# FPGA_bank0_vss.net
KiCad netlist of a schematic drawn in Altium Designer
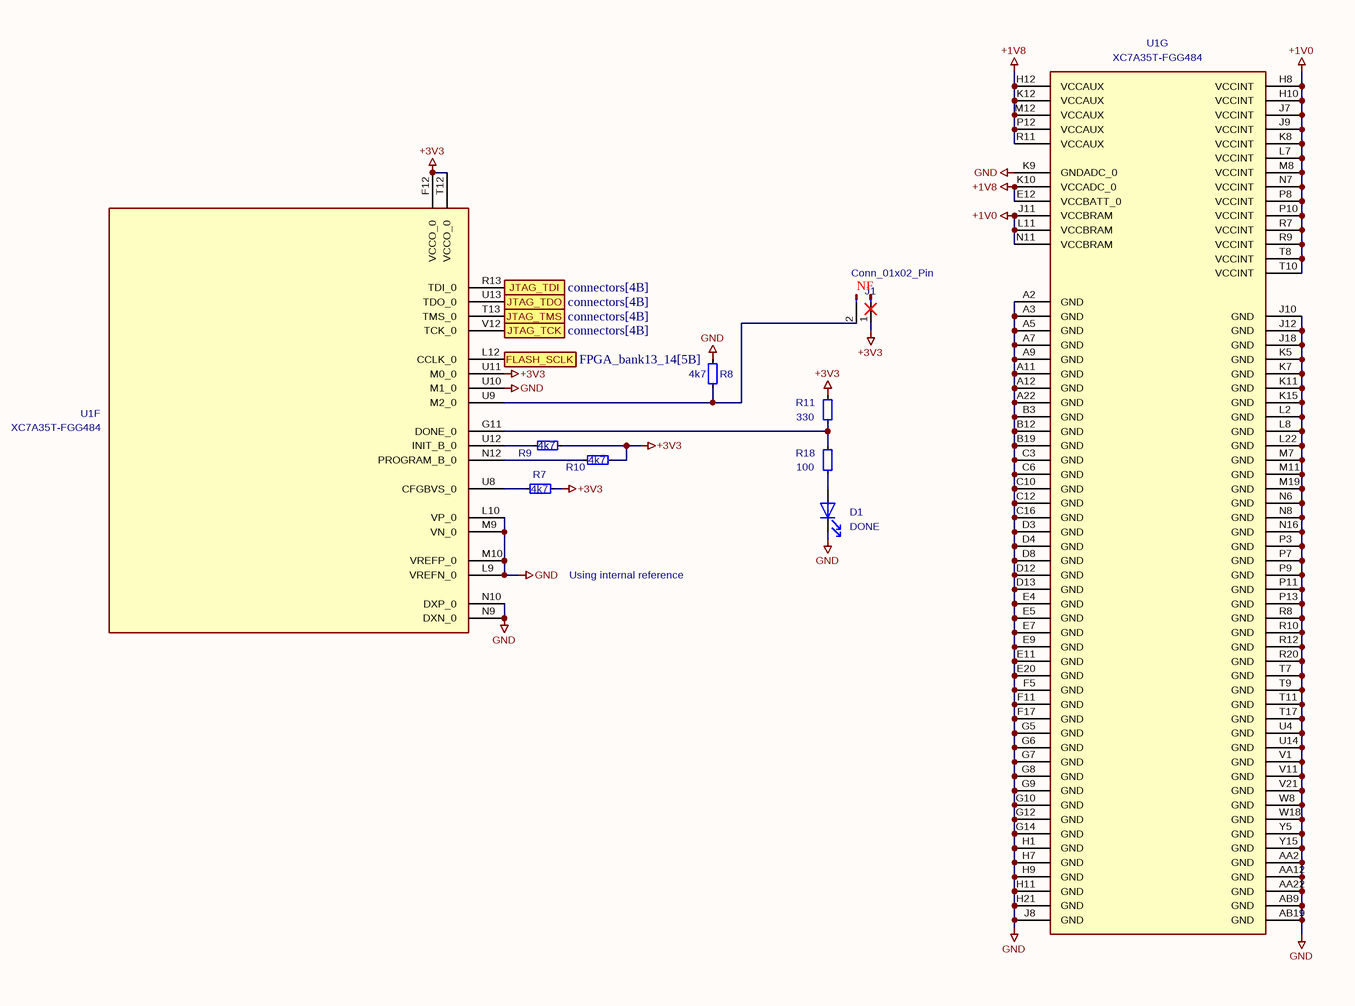
[diagram p0: FPGA_bank0_vss.SchDoc]

(export (version "E")
  (design (tool "Eeschema 10.0.6"))
  (components
    (comp (ref "D1") (value "DONE") (footprint "LED_0603_1608Metric") (libsource (lib "Device") (part "LED")))
    (comp (ref "J1")
      (value "Conn_01x02_Pin")
      (footprint "PinHeader_1x02_P2.54mm_Vertical")
      (libsource (lib "Connector") (part "Conn_01x02_Pin"))
    )
    (comp (ref "R7") (value "4k7") (footprint "R_0402_1005Metric") (libsource (lib "") (part "R_Small_1")))
    (comp (ref "R8")
      (value "4k7")
      (footprint "R_0402_1005Metric")
      (libsource (lib "Device") (part "R_Small"))
    )
    (comp (ref "R9") (value "4k7") (footprint "R_0402_1005Metric") (libsource (lib "") (part "R_Small_1")))
    (comp (ref "R10") (value "4k7") (footprint "R_0402_1005Metric") (libsource (lib "") (part "R_Small_1")))
    (comp (ref "R11")
      (value "330")
      (footprint "R_0402_1005Metric")
      (libsource (lib "Device") (part "R_Small"))
    )
    (comp (ref "R18")
      (value "100")
      (footprint "R_0402_1005Metric")
      (libsource (lib "Device") (part "R_Small"))
    )
    (comp (ref "U1")
      (value "XC7A35T-FGG484")
      (footprint "FB-BGA-484_23.0x23.0mm_Layout22x22_P1.0mm")
      (libsource (lib "som_fpga") (part "XC7A35T-FGG484"))
    )
  )
  (nets
    (net (code "1") (name "+1V0") (class "Default")
      (node (ref "U1") (pin "H10") (pinfunction "VCCINT_H10") (pintype "passive"))
      (node (ref "U1") (pin "H8") (pinfunction "VCCINT_H8") (pintype "passive"))
      (node (ref "U1") (pin "J11") (pinfunction "VCCBRAM_J11") (pintype "passive"))
      (node (ref "U1") (pin "J7") (pinfunction "VCCINT_J7") (pintype "passive"))
      (node (ref "U1") (pin "J9") (pinfunction "VCCINT_J9") (pintype "passive"))
      (node (ref "U1") (pin "K8") (pinfunction "VCCINT_K8") (pintype "passive"))
      (node (ref "U1") (pin "L11") (pinfunction "VCCBRAM_L11") (pintype "passive"))
      (node (ref "U1") (pin "L7") (pinfunction "VCCINT_L7") (pintype "passive"))
      (node (ref "U1") (pin "M8") (pinfunction "VCCINT_M8") (pintype "passive"))
      (node (ref "U1") (pin "N11") (pinfunction "VCCBRAM_N11") (pintype "passive"))
      (node (ref "U1") (pin "N7") (pinfunction "VCCINT_N7") (pintype "passive"))
      (node (ref "U1") (pin "P10") (pinfunction "VCCINT_P10") (pintype "passive"))
      (node (ref "U1") (pin "P8") (pinfunction "VCCINT_P8") (pintype "passive"))
      (node (ref "U1") (pin "R7") (pinfunction "VCCINT_R7") (pintype "passive"))
      (node (ref "U1") (pin "R9") (pinfunction "VCCINT_R9") (pintype "passive"))
      (node (ref "U1") (pin "T10") (pinfunction "VCCINT_T10") (pintype "passive"))
      (node (ref "U1") (pin "T8") (pinfunction "VCCINT_T8") (pintype "passive"))
    )
    (net (code "2") (name "+1V8") (class "Default")
      (node (ref "U1") (pin "E12") (pinfunction "VCCBATT_0_E12") (pintype "passive"))
      (node (ref "U1") (pin "H12") (pinfunction "VCCAUX_H12") (pintype "passive"))
      (node (ref "U1") (pin "K10") (pinfunction "VCCADC_0_K10") (pintype "passive"))
      (node (ref "U1") (pin "K12") (pinfunction "VCCAUX_K12") (pintype "passive"))
      (node (ref "U1") (pin "M12") (pinfunction "VCCAUX_M12") (pintype "passive"))
      (node (ref "U1") (pin "P12") (pinfunction "VCCAUX_P12") (pintype "passive"))
      (node (ref "U1") (pin "R11") (pinfunction "VCCAUX_R11") (pintype "passive"))
    )
    (net (code "3") (name "+3V3") (class "Default")
      (node (ref "J1") (pin "1") (pinfunction "Pin_1_1") (pintype "passive"))
      (node (ref "R10") (pin "2") (pinfunction "2_2") (pintype "passive"))
      (node (ref "R11") (pin "2") (pinfunction "2_2") (pintype "passive"))
      (node (ref "R7") (pin "2") (pinfunction "2_2") (pintype "passive"))
      (node (ref "R9") (pin "2") (pinfunction "2_2") (pintype "passive"))
      (node (ref "U1") (pin "F12") (pinfunction "VCCO_0_F12") (pintype "passive"))
      (node (ref "U1") (pin "T12") (pinfunction "VCCO_0_T12") (pintype "passive"))
      (node (ref "U1") (pin "U11") (pinfunction "M0_0_U11") (pintype "passive"))
    )
    (net (code "4") (name "/FLASH_SCLK") (class "Default")
      (node (ref "U1") (pin "L12") (pinfunction "CCLK_0_L12") (pintype "passive"))
    )
    (net (code "5") (name "/JTAG_TCK") (class "Default")
      (node (ref "U1") (pin "V12") (pinfunction "TCK_0_V12") (pintype "passive"))
    )
    (net (code "6") (name "/JTAG_TDI") (class "Default")
      (node (ref "U1") (pin "R13") (pinfunction "TDI_0_R13") (pintype "passive"))
    )
    (net (code "7") (name "/JTAG_TDO") (class "Default")
      (node (ref "U1") (pin "U13") (pinfunction "TDO_0_U13") (pintype "passive"))
    )
    (net (code "8") (name "/JTAG_TMS") (class "Default")
      (node (ref "U1") (pin "T13") (pinfunction "TMS_0_T13") (pintype "passive"))
    )
    (net (code "9") (name "GND") (class "Default")
      (node (ref "D1") (pin "1") (pinfunction "K_1") (pintype "passive"))
      (node (ref "R8") (pin "2") (pinfunction "2_2") (pintype "passive"))
      (node (ref "U1") (pin "A11") (pinfunction "GND_A11") (pintype "passive"))
      (node (ref "U1") (pin "A12") (pinfunction "GND_A12") (pintype "passive"))
      (node (ref "U1") (pin "A2") (pinfunction "GND_A2") (pintype "passive"))
      (node (ref "U1") (pin "A22") (pinfunction "GND_A22") (pintype "passive"))
      (node (ref "U1") (pin "A3") (pinfunction "GND_A3") (pintype "passive"))
      (node (ref "U1") (pin "A5") (pinfunction "GND_A5") (pintype "passive"))
      (node (ref "U1") (pin "A7") (pinfunction "GND_A7") (pintype "passive"))
      (node (ref "U1") (pin "A9") (pinfunction "GND_A9") (pintype "passive"))
      (node (ref "U1") (pin "AA12") (pinfunction "GND_AA12") (pintype "passive"))
      (node (ref "U1") (pin "AA2") (pinfunction "GND_AA2") (pintype "passive"))
      (node (ref "U1") (pin "AA22") (pinfunction "GND_AA22") (pintype "passive"))
      (node (ref "U1") (pin "AB19") (pinfunction "GND_AB19") (pintype "passive"))
      (node (ref "U1") (pin "AB9") (pinfunction "GND_AB9") (pintype "passive"))
      (node (ref "U1") (pin "B12") (pinfunction "GND_B12") (pintype "passive"))
      (node (ref "U1") (pin "B19") (pinfunction "GND_B19") (pintype "passive"))
      (node (ref "U1") (pin "B3") (pinfunction "GND_B3") (pintype "passive"))
      (node (ref "U1") (pin "C10") (pinfunction "GND_C10") (pintype "passive"))
      (node (ref "U1") (pin "C12") (pinfunction "GND_C12") (pintype "passive"))
      (node (ref "U1") (pin "C16") (pinfunction "GND_C16") (pintype "passive"))
      (node (ref "U1") (pin "C3") (pinfunction "GND_C3") (pintype "passive"))
      (node (ref "U1") (pin "C6") (pinfunction "GND_C6") (pintype "passive"))
      (node (ref "U1") (pin "D12") (pinfunction "GND_D12") (pintype "passive"))
      (node (ref "U1") (pin "D13") (pinfunction "GND_D13") (pintype "passive"))
      (node (ref "U1") (pin "D3") (pinfunction "GND_D3") (pintype "passive"))
      (node (ref "U1") (pin "D4") (pinfunction "GND_D4") (pintype "passive"))
      (node (ref "U1") (pin "D8") (pinfunction "GND_D8") (pintype "passive"))
      (node (ref "U1") (pin "E11") (pinfunction "GND_E11") (pintype "passive"))
      (node (ref "U1") (pin "E20") (pinfunction "GND_E20") (pintype "passive"))
      (node (ref "U1") (pin "E4") (pinfunction "GND_E4") (pintype "passive"))
      (node (ref "U1") (pin "E5") (pinfunction "GND_E5") (pintype "passive"))
      (node (ref "U1") (pin "E7") (pinfunction "GND_E7") (pintype "passive"))
      (node (ref "U1") (pin "E9") (pinfunction "GND_E9") (pintype "passive"))
      (node (ref "U1") (pin "F11") (pinfunction "GND_F11") (pintype "passive"))
      (node (ref "U1") (pin "F17") (pinfunction "GND_F17") (pintype "passive"))
      (node (ref "U1") (pin "F5") (pinfunction "GND_F5") (pintype "passive"))
      (node (ref "U1") (pin "G10") (pinfunction "GND_G10") (pintype "passive"))
      (node (ref "U1") (pin "G12") (pinfunction "GND_G12") (pintype "passive"))
      (node (ref "U1") (pin "G14") (pinfunction "GND_G14") (pintype "passive"))
      (node (ref "U1") (pin "G5") (pinfunction "GND_G5") (pintype "passive"))
      (node (ref "U1") (pin "G6") (pinfunction "GND_G6") (pintype "passive"))
      (node (ref "U1") (pin "G7") (pinfunction "GND_G7") (pintype "passive"))
      (node (ref "U1") (pin "G8") (pinfunction "GND_G8") (pintype "passive"))
      (node (ref "U1") (pin "G9") (pinfunction "GND_G9") (pintype "passive"))
      (node (ref "U1") (pin "H1") (pinfunction "GND_H1") (pintype "passive"))
      (node (ref "U1") (pin "H11") (pinfunction "GND_H11") (pintype "passive"))
      (node (ref "U1") (pin "H21") (pinfunction "GND_H21") (pintype "passive"))
      (node (ref "U1") (pin "H7") (pinfunction "GND_H7") (pintype "passive"))
      (node (ref "U1") (pin "H9") (pinfunction "GND_H9") (pintype "passive"))
      (node (ref "U1") (pin "J10") (pinfunction "GND_J10") (pintype "passive"))
      (node (ref "U1") (pin "J12") (pinfunction "GND_J12") (pintype "passive"))
      (node (ref "U1") (pin "J18") (pinfunction "GND_J18") (pintype "passive"))
      (node (ref "U1") (pin "J8") (pinfunction "GND_J8") (pintype "passive"))
      (node (ref "U1") (pin "K11") (pinfunction "GND_K11") (pintype "passive"))
      (node (ref "U1") (pin "K15") (pinfunction "GND_K15") (pintype "passive"))
      (node (ref "U1") (pin "K5") (pinfunction "GND_K5") (pintype "passive"))
      (node (ref "U1") (pin "K7") (pinfunction "GND_K7") (pintype "passive"))
      (node (ref "U1") (pin "K9") (pinfunction "GNDADC_0_K9") (pintype "passive"))
      (node (ref "U1") (pin "L10") (pinfunction "VP_0_L10") (pintype "passive"))
      (node (ref "U1") (pin "L2") (pinfunction "GND_L2") (pintype "passive"))
      (node (ref "U1") (pin "L22") (pinfunction "GND_L22") (pintype "passive"))
      (node (ref "U1") (pin "L8") (pinfunction "GND_L8") (pintype "passive"))
      (node (ref "U1") (pin "L9") (pinfunction "VREFN_0_L9") (pintype "passive"))
      (node (ref "U1") (pin "M10") (pinfunction "VREFP_0_M10") (pintype "passive"))
      (node (ref "U1") (pin "M11") (pinfunction "GND_M11") (pintype "passive"))
      (node (ref "U1") (pin "M19") (pinfunction "GND_M19") (pintype "passive"))
      (node (ref "U1") (pin "M7") (pinfunction "GND_M7") (pintype "passive"))
      (node (ref "U1") (pin "M9") (pinfunction "VN_0_M9") (pintype "passive"))
      (node (ref "U1") (pin "N10") (pinfunction "DXP_0_N10") (pintype "passive"))
      (node (ref "U1") (pin "N16") (pinfunction "GND_N16") (pintype "passive"))
      (node (ref "U1") (pin "N6") (pinfunction "GND_N6") (pintype "passive"))
      (node (ref "U1") (pin "N8") (pinfunction "GND_N8") (pintype "passive"))
      (node (ref "U1") (pin "N9") (pinfunction "DXN_0_N9") (pintype "passive"))
      (node (ref "U1") (pin "P11") (pinfunction "GND_P11") (pintype "passive"))
      (node (ref "U1") (pin "P13") (pinfunction "GND_P13") (pintype "passive"))
      (node (ref "U1") (pin "P3") (pinfunction "GND_P3") (pintype "passive"))
      (node (ref "U1") (pin "P7") (pinfunction "GND_P7") (pintype "passive"))
      (node (ref "U1") (pin "P9") (pinfunction "GND_P9") (pintype "passive"))
      (node (ref "U1") (pin "R10") (pinfunction "GND_R10") (pintype "passive"))
      (node (ref "U1") (pin "R12") (pinfunction "GND_R12") (pintype "passive"))
      (node (ref "U1") (pin "R20") (pinfunction "GND_R20") (pintype "passive"))
      (node (ref "U1") (pin "R8") (pinfunction "GND_R8") (pintype "passive"))
      (node (ref "U1") (pin "T11") (pinfunction "GND_T11") (pintype "passive"))
      (node (ref "U1") (pin "T17") (pinfunction "GND_T17") (pintype "passive"))
      (node (ref "U1") (pin "T7") (pinfunction "GND_T7") (pintype "passive"))
      (node (ref "U1") (pin "T9") (pinfunction "GND_T9") (pintype "passive"))
      (node (ref "U1") (pin "U10") (pinfunction "M1_0_U10") (pintype "passive"))
      (node (ref "U1") (pin "U14") (pinfunction "GND_U14") (pintype "passive"))
      (node (ref "U1") (pin "U4") (pinfunction "GND_U4") (pintype "passive"))
      (node (ref "U1") (pin "V1") (pinfunction "GND_V1") (pintype "passive"))
      (node (ref "U1") (pin "V11") (pinfunction "GND_V11") (pintype "passive"))
      (node (ref "U1") (pin "V21") (pinfunction "GND_V21") (pintype "passive"))
      (node (ref "U1") (pin "W18") (pinfunction "GND_W18") (pintype "passive"))
      (node (ref "U1") (pin "W8") (pinfunction "GND_W8") (pintype "passive"))
      (node (ref "U1") (pin "Y15") (pinfunction "GND_Y15") (pintype "passive"))
      (node (ref "U1") (pin "Y5") (pinfunction "GND_Y5") (pintype "passive"))
    )
    (net (code "10") (name "Net-(D1-A)") (class "Default")
      (node (ref "D1") (pin "2") (pinfunction "A_2") (pintype "passive"))
      (node (ref "R18") (pin "1") (pinfunction "1_1") (pintype "passive"))
    )
    (net (code "11") (name "Net-(J1-Pin_2)") (class "Default")
      (node (ref "J1") (pin "2") (pinfunction "Pin_2_2") (pintype "passive"))
      (node (ref "R8") (pin "1") (pinfunction "1_1") (pintype "passive"))
      (node (ref "U1") (pin "U9") (pinfunction "M2_0_U9") (pintype "passive"))
    )
    (net (code "12") (name "Net-(U1F-CFGBVS_0)") (class "Default")
      (node (ref "R7") (pin "1") (pinfunction "1_1") (pintype "passive"))
      (node (ref "U1") (pin "U8") (pinfunction "CFGBVS_0_U8") (pintype "passive"))
    )
    (net (code "13") (name "Net-(U1F-DONE_0)") (class "Default")
      (node (ref "R11") (pin "1") (pinfunction "1_1") (pintype "passive"))
      (node (ref "R18") (pin "2") (pinfunction "2_2") (pintype "passive"))
      (node (ref "U1") (pin "G11") (pinfunction "DONE_0_G11") (pintype "passive"))
    )
    (net (code "14") (name "Net-(U1F-INIT_B_0)") (class "Default")
      (node (ref "R9") (pin "1") (pinfunction "1_1") (pintype "passive"))
      (node (ref "U1") (pin "U12") (pinfunction "INIT_B_0_U12") (pintype "passive"))
    )
    (net (code "15") (name "Net-(U1F-PROGRAM_B_0)") (class "Default")
      (node (ref "R10") (pin "1") (pinfunction "1_1") (pintype "passive"))
      (node (ref "U1") (pin "N12") (pinfunction "PROGRAM_B_0_N12") (pintype "passive"))
    )
  )
)
